# MK66F.net
KiCad netlist of a schematic drawn in Altium Designer
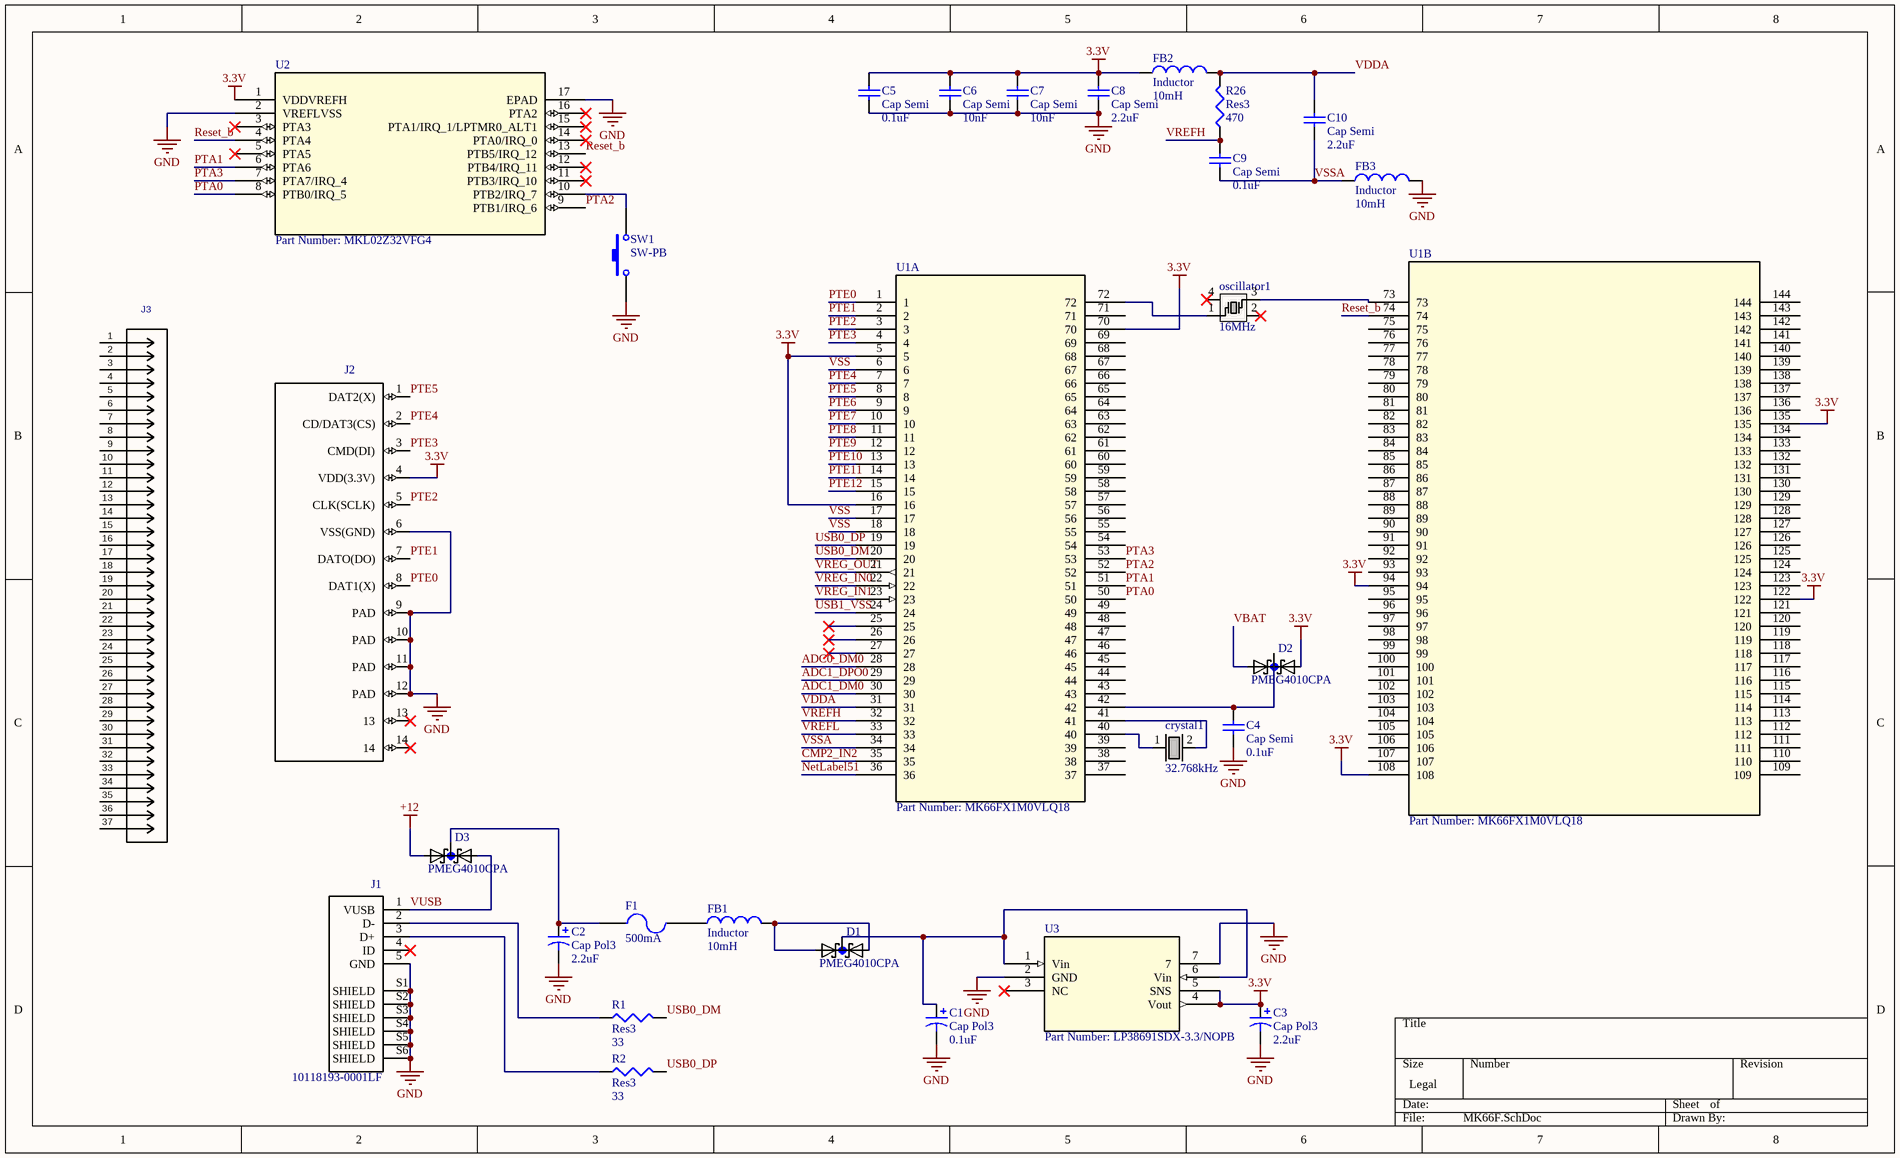
[diagram p0: MK66F.SchDoc]

(export (version "E")
  (design (tool "Eeschema 10.0.6"))
  (components
    (comp (ref "C1")
      (value "Cap Pol3")
      (footprint "C1206")
      (description "Polarized Capacitor (Surface Mount)")
      (fields (field (name "ALTIUM_VALUE") "0.1uF") (field (name "PUBLISHER") "Altium Limited"))
      (libsource (lib "Miscellaneous Devices") (part "Cap Pol3"))
    )
    (comp (ref "C2")
      (value "Cap Pol3")
      (footprint "C1206")
      (description "Polarized Capacitor (Surface Mount)")
      (fields (field (name "ALTIUM_VALUE") "2.2uF") (field (name "PUBLISHER") "Altium Limited"))
      (libsource (lib "Miscellaneous Devices") (part "Cap Pol3"))
    )
    (comp (ref "C3")
      (value "Cap Pol3")
      (footprint "C1206")
      (description "Polarized Capacitor (Surface Mount)")
      (fields (field (name "ALTIUM_VALUE") "2.2uF") (field (name "PUBLISHER") "Altium Limited"))
      (libsource (lib "Miscellaneous Devices") (part "Cap Pol3"))
    )
    (comp (ref "C4")
      (value "Cap Semi")
      (footprint "C1206")
      (description "Capacitor (Semiconductor SIM Model)")
      (fields (field (name "ALTIUM_VALUE") "0.1uF") (field (name "PUBLISHER") "Altium Limited"))
      (libsource (lib "Miscellaneous Devices") (part "Cap Semi"))
    )
    (comp (ref "C5")
      (value "Cap Semi")
      (footprint "C1206")
      (description "Capacitor (Semiconductor SIM Model)")
      (fields (field (name "ALTIUM_VALUE") "0.1uF") (field (name "PUBLISHER") "Altium Limited"))
      (libsource (lib "Miscellaneous Devices") (part "Cap Semi"))
    )
    (comp (ref "C6")
      (value "Cap Semi")
      (footprint "C1206")
      (description "Capacitor (Semiconductor SIM Model)")
      (fields (field (name "ALTIUM_VALUE") "10nF") (field (name "PUBLISHER") "Altium Limited"))
      (libsource (lib "Miscellaneous Devices") (part "Cap Semi"))
    )
    (comp (ref "C7")
      (value "Cap Semi")
      (footprint "C1206")
      (description "Capacitor (Semiconductor SIM Model)")
      (fields (field (name "ALTIUM_VALUE") "10nF") (field (name "PUBLISHER") "Altium Limited"))
      (libsource (lib "Miscellaneous Devices") (part "Cap Semi"))
    )
    (comp (ref "C8")
      (value "Cap Semi")
      (footprint "C1206")
      (description "Capacitor (Semiconductor SIM Model)")
      (fields (field (name "ALTIUM_VALUE") "2.2uF") (field (name "PUBLISHER") "Altium Limited"))
      (libsource (lib "Miscellaneous Devices") (part "Cap Semi"))
    )
    (comp (ref "C9")
      (value "Cap Semi")
      (footprint "C1206")
      (description "Capacitor (Semiconductor SIM Model)")
      (fields (field (name "ALTIUM_VALUE") "0.1uF") (field (name "PUBLISHER") "Altium Limited"))
      (libsource (lib "Miscellaneous Devices") (part "Cap Semi"))
    )
    (comp (ref "C10")
      (value "Cap Semi")
      (footprint "C1206")
      (description "Capacitor (Semiconductor SIM Model)")
      (fields (field (name "ALTIUM_VALUE") "2.2uF") (field (name "PUBLISHER") "Altium Limited"))
      (libsource (lib "Miscellaneous Devices") (part "Cap Semi"))
    )
    (comp (ref "crystal1")
      (value "32.768kHz")
      (footprint "ECS-.327-CDX-1128")
      (fields (field (name "Comment") "SMD_Crystal"))
      (libsource (lib "ECS-.327-CDX-1128") (part "ECS-.327-CDX-1128"))
    )
    (comp (ref "D1")
      (value "PMEG4010CPA")
      (footprint "*SOT1061")
      (fields (field (name "MF") "Nexperia USA") (field (name "DIGI-KEY_PART_NUMBER") "1727-5212-1-ND"))
      (libsource (lib "PMEG4010CPA") (part "PMEG4010CPA"))
    )
    (comp (ref "D2")
      (value "PMEG4010CPA")
      (footprint "*SOT1061")
      (fields (field (name "MF") "Nexperia USA") (field (name "DIGI-KEY_PART_NUMBER") "1727-5212-1-ND"))
      (libsource (lib "PMEG4010CPA") (part "PMEG4010CPA"))
    )
    (comp (ref "D3")
      (value "PMEG4010CPA")
      (footprint "*SOT1061")
      (fields (field (name "MF") "Nexperia USA") (field (name "DIGI-KEY_PART_NUMBER") "1727-5212-1-ND"))
      (libsource (lib "PMEG4010CPA") (part "PMEG4010CPA"))
    )
    (comp (ref "F1")
      (value "500mA")
      (footprint "RESC3216X125N")
      (description "Fuse")
      (fields (field (name "PUBLISHER") "Altium Limited"))
      (libsource (lib "Miscellaneous Devices") (part "Fuse 2"))
    )
    (comp (ref "FB1")
      (value "Inductor")
      (footprint "J1-0603")
      (fields (field (name "ALTIUM_VALUE") "10mH") (field (name "PUBLISHER") "Altium Limited"))
      (libsource (lib "Miscellaneous Devices") (part "Inductor"))
    )
    (comp (ref "FB2")
      (value "Inductor")
      (footprint "J1-0603")
      (fields (field (name "ALTIUM_VALUE") "10mH") (field (name "PUBLISHER") "Altium Limited"))
      (libsource (lib "Miscellaneous Devices") (part "Inductor"))
    )
    (comp (ref "FB3")
      (value "Inductor")
      (footprint "J1-0603")
      (fields (field (name "ALTIUM_VALUE") "10mH") (field (name "PUBLISHER") "Altium Limited"))
      (libsource (lib "Miscellaneous Devices") (part "Inductor"))
    )
    (comp (ref "J1")
      (value "10118193-0001LF")
      (footprint "FCI_10118193-0001LF_10118193-0001LF(Primary)")
      (description "Single Port 5 Contact Shielded SMT MICRO USB B-Type Receptacle")
      (fields (field (name "MF") "Amphenol FCI") (field (name "DIGI-KEY_PART_NUMBER") "609-4616-1-ND"))
      (libsource (lib "10118193-0001LF") (part "10118193-0001LF"))
    )
    (comp (ref "J2")
      (value "1140084168")
      (footprint "*1140084168")
      (description "Conn; IC Socket; Micro SD; Right Angle; PCB Mount; MicroSD Ser.")
      (fields (field (name "DIGI-KEY_PART_NUMBER") "114-00841-68-1-ND") (field (name "MF") "Amphenol ICC"))
      (libsource (lib "1140084168") (part "1140084168"))
    )
    (comp (ref "J3")
      (value "5747847-4")
      (footprint "SPGA48x11 - duplicate")
      (libsource (lib "5747847-4") (part "5747847-4"))
    )
    (comp (ref "oscillator1")
      (value "16MHz")
      (footprint "ECS-160-8-30B-CKM")
      (fields (field (name "Comment") "SMD_oscillator"))
      (libsource (lib "ECS-160-8-30B-CKM") (part "ECS-160-8-30B-CKM"))
    )
    (comp (ref "R1")
      (value "Res3")
      (footprint "J1-0603")
      (description "Resistor")
      (fields (field (name "ALTIUM_VALUE") "33") (field (name "PUBLISHER") "Altium Limited"))
      (libsource (lib "Miscellaneous Devices") (part "Res3"))
    )
    (comp (ref "R2")
      (value "Res3")
      (footprint "J1-0603")
      (description "Resistor")
      (fields (field (name "ALTIUM_VALUE") "33") (field (name "PUBLISHER") "Altium Limited"))
      (libsource (lib "Miscellaneous Devices") (part "Res3"))
    )
    (comp (ref "R26")
      (value "Res3")
      (footprint "J1-0603")
      (description "Resistor")
      (fields (field (name "ALTIUM_VALUE") "470") (field (name "PUBLISHER") "Altium Limited"))
      (libsource (lib "Miscellaneous Devices") (part "Res3"))
    )
    (comp (ref "SW1")
      (value "SW-PB")
      (footprint "P13348SCT-ND")
      (description "Switch")
      (fields (field (name "PUBLISHER") "Altium Limited"))
      (libsource (lib "Miscellaneous Devices") (part "SW-PB"))
    )
    (comp (ref "U1")
      (value "Part Number: MK66FX1M0VLQ18")
      (footprint "98ASS23177W")
      (description "No Description Available")
      (fields
        (field (name "MANUFACTURER_PART_NUMBER") "MK66FX1M0VLQ18")
        (field (name "COPYRIGHT") "Copyright (C) 2016 Accelerated Designs. All rights reserved")
      )
      (libsource (lib "2019-07-06_08-00-28") (part "MK66FX1M0VLQ18"))
    )
    (comp (ref "U2")
      (value "Part Number: MKL02Z32VFG4")
      (footprint "QFN-16_3X3X0.65")
      (description "No Description Available")
      (fields
        (field (name "MANUFACTURER_PART_NUMBER") "MKL02Z32VFG4")
        (field (name "COPYRIGHT") "Copyright (C) 2016 Accelerated Designs. All rights reserved")
      )
      (libsource (lib "2019-07-30_08-24-30") (part "MKL02Z32VFG4"))
    )
    (comp (ref "U3")
      (value "Part Number: LP38691SDX-3.3/NOPB")
      (footprint "SDE06A")
      (description "No Description Available")
      (fields
        (field (name "MANUFACTURER_PART_NUMBER") "LP38691SDX-3.3/NOPB")
        (field (name "COPYRIGHT") "Copyright (C) 2018 Accelerated Designs. All rights reserved")
      )
      (libsource (lib "LP38691SDX_3") (part "LP38691SDX-3.3/N"))
    )
  )
  (nets
    (net (code "1") (name "+12") (class "Default")
      (node (ref "D3") (pin "1") (pinfunction "A1_1") (pintype "passive"))
    )
    (net (code "2") (name "/ADC0_DM0") (class "Default")
      (node (ref "U1") (pin "28") (pinfunction "28_28") (pintype "passive"))
    )
    (net (code "3") (name "/ADC1_DM0") (class "Default")
      (node (ref "U1") (pin "30") (pinfunction "30_30") (pintype "passive"))
    )
    (net (code "4") (name "/ADC1_DPO0") (class "Default")
      (node (ref "U1") (pin "29") (pinfunction "29_29") (pintype "passive"))
    )
    (net (code "5") (name "/CMP2_IN2") (class "Default")
      (node (ref "U1") (pin "35") (pinfunction "35_35") (pintype "passive"))
    )
    (net (code "6") (name "/NetLabel51") (class "Default")
      (node (ref "U1") (pin "36") (pinfunction "36_36") (pintype "passive"))
    )
    (net (code "7") (name "/PTA0") (class "Default")
      (node (ref "U1") (pin "50") (pinfunction "50_50") (pintype "passive"))
      (node (ref "U2") (pin "8") (pinfunction "PTB0/IRQ_5_8") (pintype "bidirectional"))
    )
    (net (code "8") (name "/PTA1") (class "Default")
      (node (ref "U1") (pin "51") (pinfunction "51_51") (pintype "passive"))
      (node (ref "U2") (pin "6") (pinfunction "PTA6_6") (pintype "bidirectional"))
    )
    (net (code "9") (name "/PTA2") (class "Default")
      (node (ref "U1") (pin "52") (pinfunction "52_52") (pintype "passive"))
      (node (ref "U2") (pin "9") (pinfunction "PTB1/IRQ_6_9") (pintype "bidirectional"))
    )
    (net (code "10") (name "/PTA3") (class "Default")
      (node (ref "U1") (pin "53") (pinfunction "53_53") (pintype "passive"))
      (node (ref "U2") (pin "7") (pinfunction "PTA7/IRQ_4_7") (pintype "bidirectional"))
    )
    (net (code "11") (name "/PTE0") (class "Default")
      (node (ref "J2") (pin "8") (pinfunction "DAT1(X)_8") (pintype "bidirectional"))
      (node (ref "U1") (pin "1") (pinfunction "1_1") (pintype "passive"))
    )
    (net (code "12") (name "/PTE1") (class "Default")
      (node (ref "J2") (pin "7") (pinfunction "DATO(DO)_7") (pintype "bidirectional"))
      (node (ref "U1") (pin "2") (pinfunction "2_2") (pintype "passive"))
    )
    (net (code "13") (name "/PTE2") (class "Default")
      (node (ref "J2") (pin "5") (pinfunction "CLK(SCLK)_5") (pintype "bidirectional"))
      (node (ref "U1") (pin "3") (pinfunction "3_3") (pintype "passive"))
    )
    (net (code "14") (name "/PTE3") (class "Default")
      (node (ref "J2") (pin "3") (pinfunction "CMD(DI)_3") (pintype "bidirectional"))
      (node (ref "U1") (pin "4") (pinfunction "4_4") (pintype "passive"))
    )
    (net (code "15") (name "/PTE4") (class "Default")
      (node (ref "J2") (pin "2") (pinfunction "CD/DAT3(CS)_2") (pintype "bidirectional"))
      (node (ref "U1") (pin "7") (pinfunction "7_7") (pintype "passive"))
    )
    (net (code "16") (name "/PTE5") (class "Default")
      (node (ref "J2") (pin "1") (pinfunction "DAT2(X)_1") (pintype "bidirectional"))
      (node (ref "U1") (pin "8") (pinfunction "8_8") (pintype "passive"))
    )
    (net (code "17") (name "/PTE6") (class "Default")
      (node (ref "U1") (pin "9") (pinfunction "9_9") (pintype "passive"))
    )
    (net (code "18") (name "/PTE7") (class "Default")
      (node (ref "U1") (pin "10") (pinfunction "10_10") (pintype "passive"))
    )
    (net (code "19") (name "/PTE8") (class "Default")
      (node (ref "U1") (pin "11") (pinfunction "11_11") (pintype "passive"))
    )
    (net (code "20") (name "/PTE9") (class "Default")
      (node (ref "U1") (pin "12") (pinfunction "12_12") (pintype "passive"))
    )
    (net (code "21") (name "/PTE10") (class "Default")
      (node (ref "U1") (pin "13") (pinfunction "13_13") (pintype "passive"))
    )
    (net (code "22") (name "/PTE11") (class "Default")
      (node (ref "U1") (pin "14") (pinfunction "14_14") (pintype "passive"))
    )
    (net (code "23") (name "/PTE12") (class "Default")
      (node (ref "U1") (pin "15") (pinfunction "15_15") (pintype "passive"))
    )
    (net (code "24") (name "/Reset_b") (class "Default")
      (node (ref "U1") (pin "74") (pinfunction "74_74") (pintype "passive"))
      (node (ref "U2") (pin "13") (pinfunction "PTB5/IRQ_12_13") (pintype "bidirectional"))
      (node (ref "U2") (pin "4") (pinfunction "PTA4_4") (pintype "bidirectional"))
    )
    (net (code "25") (name "/USB0_DM") (class "Default")
      (node (ref "R1") (pin "2") (pinfunction "2_2") (pintype "passive"))
      (node (ref "U1") (pin "20") (pinfunction "20_20") (pintype "passive"))
    )
    (net (code "26") (name "/USB0_DP") (class "Default")
      (node (ref "R2") (pin "2") (pinfunction "2_2") (pintype "passive"))
      (node (ref "U1") (pin "19") (pinfunction "19_19") (pintype "passive"))
    )
    (net (code "27") (name "/USB1_VSS") (class "Default")
      (node (ref "U1") (pin "24") (pinfunction "24_24") (pintype "power_in"))
    )
    (net (code "28") (name "/VBAT") (class "Default")
      (node (ref "D2") (pin "1") (pinfunction "A1_1") (pintype "passive"))
    )
    (net (code "29") (name "/VDDA") (class "Default")
      (node (ref "C10") (pin "2") (pinfunction "2_2") (pintype "passive"))
      (node (ref "FB2") (pin "2") (pinfunction "2_2") (pintype "passive"))
      (node (ref "R26") (pin "2") (pinfunction "2_2") (pintype "passive"))
      (node (ref "U1") (pin "31") (pinfunction "31_31") (pintype "power_in"))
    )
    (net (code "30") (name "/VREFH") (class "Default")
      (node (ref "C9") (pin "2") (pinfunction "2_2") (pintype "passive"))
      (node (ref "R26") (pin "1") (pinfunction "1_1") (pintype "passive"))
      (node (ref "U1") (pin "32") (pinfunction "32_32") (pintype "power_in"))
    )
    (net (code "31") (name "/VREFL") (class "Default")
      (node (ref "U1") (pin "33") (pinfunction "33_33") (pintype "power_in"))
    )
    (net (code "32") (name "/VREG_IN0") (class "Default")
      (node (ref "U1") (pin "22") (pinfunction "22_22") (pintype "input"))
    )
    (net (code "33") (name "/VREG_IN1") (class "Default")
      (node (ref "U1") (pin "23") (pinfunction "23_23") (pintype "input"))
    )
    (net (code "34") (name "/VREG_OUT") (class "Default")
      (node (ref "U1") (pin "21") (pinfunction "21_21") (pintype "output"))
    )
    (net (code "35") (name "/VSS") (class "Default")
      (node (ref "U1") (pin "17") (pinfunction "17_17") (pintype "power_in"))
      (node (ref "U1") (pin "18") (pinfunction "18_18") (pintype "power_in"))
      (node (ref "U1") (pin "6") (pinfunction "6_6") (pintype "power_in"))
    )
    (net (code "36") (name "/VSSA") (class "Default")
      (node (ref "C10") (pin "1") (pinfunction "1_1") (pintype "passive"))
      (node (ref "C9") (pin "1") (pinfunction "1_1") (pintype "passive"))
      (node (ref "FB3") (pin "1") (pinfunction "1_1") (pintype "passive"))
      (node (ref "U1") (pin "34") (pinfunction "34_34") (pintype "power_in"))
    )
    (net (code "37") (name "/VUSB") (class "Default")
      (node (ref "D3") (pin "2") (pinfunction "A2_2") (pintype "passive"))
      (node (ref "J1") (pin "1") (pinfunction "VUSB_1") (pintype "passive"))
    )
    (net (code "38") (name "3.3V") (class "Default")
      (node (ref "C3") (pin "1") (pinfunction "1_1") (pintype "passive"))
      (node (ref "C5") (pin "2") (pinfunction "2_2") (pintype "passive"))
      (node (ref "C6") (pin "2") (pinfunction "2_2") (pintype "passive"))
      (node (ref "C7") (pin "2") (pinfunction "2_2") (pintype "passive"))
      (node (ref "C8") (pin "2") (pinfunction "2_2") (pintype "passive"))
      (node (ref "D2") (pin "2") (pinfunction "A2_2") (pintype "passive"))
      (node (ref "FB2") (pin "1") (pinfunction "1_1") (pintype "passive"))
      (node (ref "J2") (pin "4") (pinfunction "VDD(3.3V)_4") (pintype "bidirectional"))
      (node (ref "U1") (pin "108") (pinfunction "108_108") (pintype "power_in"))
      (node (ref "U1") (pin "122") (pinfunction "122_122") (pintype "power_in"))
      (node (ref "U1") (pin "135") (pinfunction "135_135") (pintype "power_in"))
      (node (ref "U1") (pin "16") (pinfunction "16_16") (pintype "power_in"))
      (node (ref "U1") (pin "5") (pinfunction "5_5") (pintype "power_in"))
      (node (ref "U1") (pin "70") (pinfunction "70_70") (pintype "power_in"))
      (node (ref "U1") (pin "94") (pinfunction "94_94") (pintype "power_in"))
      (node (ref "U2") (pin "1") (pinfunction "VDDVREFH_1") (pintype "power_in"))
      (node (ref "U3") (pin "4") (pinfunction "Vout_4") (pintype "output"))
      (node (ref "U3") (pin "5") (pinfunction "SNS_5") (pintype "passive"))
    )
    (net (code "39") (name "GND") (class "Default")
      (node (ref "C1") (pin "2") (pinfunction "2_2") (pintype "passive"))
      (node (ref "C2") (pin "2") (pinfunction "2_2") (pintype "passive"))
      (node (ref "C3") (pin "2") (pinfunction "2_2") (pintype "passive"))
      (node (ref "C4") (pin "1") (pinfunction "1_1") (pintype "passive"))
      (node (ref "C5") (pin "1") (pinfunction "1_1") (pintype "passive"))
      (node (ref "C6") (pin "1") (pinfunction "1_1") (pintype "passive"))
      (node (ref "C7") (pin "1") (pinfunction "1_1") (pintype "passive"))
      (node (ref "C8") (pin "1") (pinfunction "1_1") (pintype "passive"))
      (node (ref "FB3") (pin "2") (pinfunction "2_2") (pintype "passive"))
      (node (ref "J1") (pin "5") (pinfunction "GND_5") (pintype "passive"))
      (node (ref "J1") (pin "S1") (pinfunction "SHIELD_S1") (pintype "passive"))
      (node (ref "J1") (pin "S2") (pinfunction "SHIELD_S2") (pintype "passive"))
      (node (ref "J1") (pin "S3") (pinfunction "SHIELD_S3") (pintype "passive"))
      (node (ref "J1") (pin "S4") (pinfunction "SHIELD_S4") (pintype "passive"))
      (node (ref "J1") (pin "S5") (pinfunction "SHIELD_S5") (pintype "passive"))
      (node (ref "J1") (pin "S6") (pinfunction "SHIELD_S6") (pintype "passive"))
      (node (ref "J2") (pin "10") (pinfunction "PAD_10") (pintype "bidirectional"))
      (node (ref "J2") (pin "11") (pinfunction "PAD_11") (pintype "bidirectional"))
      (node (ref "J2") (pin "12") (pinfunction "PAD_12") (pintype "bidirectional"))
      (node (ref "J2") (pin "6") (pinfunction "VSS(GND)_6") (pintype "bidirectional"))
      (node (ref "J2") (pin "9") (pinfunction "PAD_9") (pintype "bidirectional"))
      (node (ref "SW1") (pin "1") (pinfunction "1_1") (pintype "passive"))
      (node (ref "U2") (pin "17") (pinfunction "EPAD_17") (pintype "passive"))
      (node (ref "U2") (pin "2") (pinfunction "VREFLVSS_2") (pintype "power_in"))
      (node (ref "U3") (pin "2") (pinfunction "GND_2") (pintype "passive"))
      (node (ref "U3") (pin "7") (pinfunction "7_7") (pintype "passive"))
    )
    (net (code "40") (name "Net-(C4-Pad2)") (class "Default")
      (node (ref "C4") (pin "2") (pinfunction "2_2") (pintype "passive"))
      (node (ref "U1") (pin "42") (pinfunction "42_42") (pintype "power_in"))
    )
    (net (code "41") (name "Net-(D1-A1)") (class "Default")
      (node (ref "D1") (pin "1") (pinfunction "A1_1") (pintype "passive"))
      (node (ref "D1") (pin "2") (pinfunction "A2_2") (pintype "passive"))
      (node (ref "FB1") (pin "2") (pinfunction "2_2") (pintype "passive"))
    )
    (net (code "42") (name "Net-(D1-K1K2)") (class "Default")
      (node (ref "C1") (pin "1") (pinfunction "1_1") (pintype "passive"))
      (node (ref "D1") (pin "3") (pinfunction "K1K2_3") (pintype "passive"))
      (node (ref "U3") (pin "1") (pinfunction "Vin_1") (pintype "input"))
      (node (ref "U3") (pin "6") (pinfunction "Vin_6") (pintype "input"))
    )
    (net (code "43") (name "Net-(D3-K1K2)") (class "Default")
      (node (ref "C2") (pin "1") (pinfunction "1_1") (pintype "passive"))
      (node (ref "D3") (pin "3") (pinfunction "K1K2_3") (pintype "passive"))
      (node (ref "F1") (pin "1") (pinfunction "1_1") (pintype "passive"))
    )
    (net (code "44") (name "Net-(F1-Pad2)") (class "Default")
      (node (ref "F1") (pin "2") (pinfunction "2_2") (pintype "passive"))
      (node (ref "FB1") (pin "1") (pinfunction "1_1") (pintype "passive"))
    )
    (net (code "45") (name "Net-(J1-D+)") (class "Default")
      (node (ref "J1") (pin "3") (pinfunction "D+_3") (pintype "passive"))
      (node (ref "R2") (pin "1") (pinfunction "1_1") (pintype "passive"))
    )
    (net (code "46") (name "Net-(J1-D-)") (class "Default")
      (node (ref "J1") (pin "2") (pinfunction "D-_2") (pintype "passive"))
      (node (ref "R1") (pin "1") (pinfunction "1_1") (pintype "passive"))
    )
    (net (code "47") (name "Net-(U1-Pad40)") (class "Default")
      (node (ref "U1") (pin "40") (pinfunction "40_40") (pintype "passive"))
      (node (ref "crystal1") (pin "1") (pinfunction "1_1") (pintype "passive"))
    )
    (net (code "48") (name "Net-(U1-Pad41)") (class "Default")
      (node (ref "U1") (pin "41") (pinfunction "41_41") (pintype "passive"))
      (node (ref "crystal1") (pin "2") (pinfunction "2_2") (pintype "passive"))
    )
    (net (code "49") (name "Net-(U1-Pad72)") (class "Default")
      (node (ref "U1") (pin "72") (pinfunction "72_72") (pintype "passive"))
      (node (ref "oscillator1") (pin "1") (pinfunction "1_1") (pintype "passive"))
    )
    (net (code "50") (name "Net-(U1-Pad73)") (class "Default")
      (node (ref "U1") (pin "73") (pinfunction "73_73") (pintype "passive"))
      (node (ref "oscillator1") (pin "3") (pinfunction "3_3") (pintype "passive"))
    )
    (net (code "51") (name "Net-(U2-PTB2{slash}IRQ_7)") (class "Default")
      (node (ref "SW1") (pin "2") (pinfunction "2_2") (pintype "passive"))
      (node (ref "U2") (pin "10") (pinfunction "PTB2/IRQ_7_10") (pintype "bidirectional"))
    )
    (net (code "52") (name "unconnected-(D2-K1K2-Pad3)") (class "Default")
      (node (ref "D2") (pin "3") (pinfunction "K1K2_3") (pintype "passive"))
    )
    (net (code "53") (name "unconnected-(J1-ID-Pad4)") (class "Default")
      (node (ref "J1") (pin "4") (pinfunction "ID_4") (pintype "passive+no_connect"))
    )
    (net (code "54") (name "unconnected-(J2-Pad13)") (class "Default")
      (node (ref "J2") (pin "13") (pinfunction "13_13") (pintype "bidirectional+no_connect"))
    )
    (net (code "55") (name "unconnected-(J2-Pad14)") (class "Default")
      (node (ref "J2") (pin "14") (pinfunction "14_14") (pintype "bidirectional+no_connect"))
    )
    (net (code "56") (name "unconnected-(J3-Pad1)") (class "Default")
      (node (ref "J3") (pin "1") (pinfunction "1_1") (pintype "passive"))
    )
    (net (code "57") (name "unconnected-(J3-Pad2)") (class "Default")
      (node (ref "J3") (pin "2") (pinfunction "2_2") (pintype "passive"))
    )
    (net (code "58") (name "unconnected-(J3-Pad3)") (class "Default")
      (node (ref "J3") (pin "3") (pinfunction "3_3") (pintype "passive"))
    )
    (net (code "59") (name "unconnected-(J3-Pad4)") (class "Default")
      (node (ref "J3") (pin "4") (pinfunction "4_4") (pintype "passive"))
    )
    (net (code "60") (name "unconnected-(J3-Pad5)") (class "Default")
      (node (ref "J3") (pin "5") (pinfunction "5_5") (pintype "passive"))
    )
    (net (code "61") (name "unconnected-(J3-Pad6)") (class "Default")
      (node (ref "J3") (pin "6") (pinfunction "6_6") (pintype "passive"))
    )
    (net (code "62") (name "unconnected-(J3-Pad7)") (class "Default")
      (node (ref "J3") (pin "7") (pinfunction "7_7") (pintype "passive"))
    )
    (net (code "63") (name "unconnected-(J3-Pad8)") (class "Default")
      (node (ref "J3") (pin "8") (pinfunction "8_8") (pintype "passive"))
    )
    (net (code "64") (name "unconnected-(J3-Pad9)") (class "Default")
      (node (ref "J3") (pin "9") (pinfunction "9_9") (pintype "passive"))
    )
    (net (code "65") (name "unconnected-(J3-Pad10)") (class "Default")
      (node (ref "J3") (pin "10") (pinfunction "10_10") (pintype "passive"))
    )
    (net (code "66") (name "unconnected-(J3-Pad11)") (class "Default")
      (node (ref "J3") (pin "11") (pinfunction "11_11") (pintype "passive"))
    )
    (net (code "67") (name "unconnected-(J3-Pad12)") (class "Default")
      (node (ref "J3") (pin "12") (pinfunction "12_12") (pintype "passive"))
    )
    (net (code "68") (name "unconnected-(J3-Pad13)") (class "Default")
      (node (ref "J3") (pin "13") (pinfunction "13_13") (pintype "passive"))
    )
    (net (code "69") (name "unconnected-(J3-Pad14)") (class "Default")
      (node (ref "J3") (pin "14") (pinfunction "14_14") (pintype "passive"))
    )
    (net (code "70") (name "unconnected-(J3-Pad15)") (class "Default")
      (node (ref "J3") (pin "15") (pinfunction "15_15") (pintype "passive"))
    )
    (net (code "71") (name "unconnected-(J3-Pad16)") (class "Default")
      (node (ref "J3") (pin "16") (pinfunction "16_16") (pintype "passive"))
    )
    (net (code "72") (name "unconnected-(J3-Pad17)") (class "Default")
      (node (ref "J3") (pin "17") (pinfunction "17_17") (pintype "passive"))
    )
    (net (code "73") (name "unconnected-(J3-Pad18)") (class "Default")
      (node (ref "J3") (pin "18") (pinfunction "18_18") (pintype "passive"))
    )
    (net (code "74") (name "unconnected-(J3-Pad19)") (class "Default")
      (node (ref "J3") (pin "19") (pinfunction "19_19") (pintype "passive"))
    )
    (net (code "75") (name "unconnected-(J3-Pad20)") (class "Default")
      (node (ref "J3") (pin "20") (pinfunction "20_20") (pintype "passive"))
    )
    (net (code "76") (name "unconnected-(J3-Pad21)") (class "Default")
      (node (ref "J3") (pin "21") (pinfunction "21_21") (pintype "passive"))
    )
    (net (code "77") (name "unconnected-(J3-Pad22)") (class "Default")
      (node (ref "J3") (pin "22") (pinfunction "22_22") (pintype "passive"))
    )
    (net (code "78") (name "unconnected-(J3-Pad23)") (class "Default")
      (node (ref "J3") (pin "23") (pinfunction "23_23") (pintype "passive"))
    )
    (net (code "79") (name "unconnected-(J3-Pad24)") (class "Default")
      (node (ref "J3") (pin "24") (pinfunction "24_24") (pintype "passive"))
    )
    (net (code "80") (name "unconnected-(J3-Pad25)") (class "Default")
      (node (ref "J3") (pin "25") (pinfunction "25_25") (pintype "passive"))
    )
    (net (code "81") (name "unconnected-(J3-Pad26)") (class "Default")
      (node (ref "J3") (pin "26") (pinfunction "26_26") (pintype "passive"))
    )
    (net (code "82") (name "unconnected-(J3-Pad27)") (class "Default")
      (node (ref "J3") (pin "27") (pinfunction "27_27") (pintype "passive"))
    )
    (net (code "83") (name "unconnected-(J3-Pad28)") (class "Default")
      (node (ref "J3") (pin "28") (pinfunction "28_28") (pintype "passive"))
    )
    (net (code "84") (name "unconnected-(J3-Pad29)") (class "Default")
      (node (ref "J3") (pin "29") (pinfunction "29_29") (pintype "passive"))
    )
    (net (code "85") (name "unconnected-(J3-Pad30)") (class "Default")
      (node (ref "J3") (pin "30") (pinfunction "30_30") (pintype "passive"))
    )
    (net (code "86") (name "unconnected-(J3-Pad31)") (class "Default")
      (node (ref "J3") (pin "31") (pinfunction "31_31") (pintype "passive"))
    )
    (net (code "87") (name "unconnected-(J3-Pad32)") (class "Default")
      (node (ref "J3") (pin "32") (pinfunction "32_32") (pintype "passive"))
    )
    (net (code "88") (name "unconnected-(J3-Pad33)") (class "Default")
      (node (ref "J3") (pin "33") (pinfunction "33_33") (pintype "passive"))
    )
    (net (code "89") (name "unconnected-(J3-Pad34)") (class "Default")
      (node (ref "J3") (pin "34") (pinfunction "34_34") (pintype "passive"))
    )
    (net (code "90") (name "unconnected-(J3-Pad35)") (class "Default")
      (node (ref "J3") (pin "35") (pinfunction "35_35") (pintype "passive"))
    )
    (net (code "91") (name "unconnected-(J3-Pad36)") (class "Default")
      (node (ref "J3") (pin "36") (pinfunction "36_36") (pintype "passive"))
    )
    (net (code "92") (name "unconnected-(J3-Pad37)") (class "Default")
      (node (ref "J3") (pin "37") (pinfunction "37_37") (pintype "passive"))
    )
    (net (code "93") (name "unconnected-(U1-Pad25)") (class "Default")
      (node (ref "U1") (pin "25") (pinfunction "25_25") (pintype "passive+no_connect"))
    )
    (net (code "94") (name "unconnected-(U1-Pad26)") (class "Default")
      (node (ref "U1") (pin "26") (pinfunction "26_26") (pintype "passive+no_connect"))
    )
    (net (code "95") (name "unconnected-(U1-Pad27)") (class "Default")
      (node (ref "U1") (pin "27") (pinfunction "27_27") (pintype "passive+no_connect"))
    )
    (net (code "96") (name "unconnected-(U1-Pad37)") (class "Default")
      (node (ref "U1") (pin "37") (pinfunction "37_37") (pintype "passive"))
    )
    (net (code "97") (name "unconnected-(U1-Pad38)") (class "Default")
      (node (ref "U1") (pin "38") (pinfunction "38_38") (pintype "passive"))
    )
    (net (code "98") (name "unconnected-(U1-Pad39)") (class "Default")
      (node (ref "U1") (pin "39") (pinfunction "39_39") (pintype "passive"))
    )
    (net (code "99") (name "unconnected-(U1-Pad43)") (class "Default")
      (node (ref "U1") (pin "43") (pinfunction "43_43") (pintype "power_in"))
    )
    (net (code "100") (name "unconnected-(U1-Pad44)") (class "Default")
      (node (ref "U1") (pin "44") (pinfunction "44_44") (pintype "power_in"))
    )
    (net (code "101") (name "unconnected-(U1-Pad45)") (class "Default")
      (node (ref "U1") (pin "45") (pinfunction "45_45") (pintype "passive"))
    )
    (net (code "102") (name "unconnected-(U1-Pad46)") (class "Default")
      (node (ref "U1") (pin "46") (pinfunction "46_46") (pintype "passive"))
    )
    (net (code "103") (name "unconnected-(U1-Pad47)") (class "Default")
      (node (ref "U1") (pin "47") (pinfunction "47_47") (pintype "passive"))
    )
    (net (code "104") (name "unconnected-(U1-Pad48)") (class "Default")
      (node (ref "U1") (pin "48") (pinfunction "48_48") (pintype "passive"))
    )
    (net (code "105") (name "unconnected-(U1-Pad49)") (class "Default")
      (node (ref "U1") (pin "49") (pinfunction "49_49") (pintype "passive"))
    )
    (net (code "106") (name "unconnected-(U1-Pad54)") (class "Default")
      (node (ref "U1") (pin "54") (pinfunction "54_54") (pintype "passive"))
    )
    (net (code "107") (name "unconnected-(U1-Pad55)") (class "Default")
      (node (ref "U1") (pin "55") (pinfunction "55_55") (pintype "passive"))
    )
    (net (code "108") (name "unconnected-(U1-Pad56)") (class "Default")
      (node (ref "U1") (pin "56") (pinfunction "56_56") (pintype "power_in"))
    )
    (net (code "109") (name "unconnected-(U1-Pad57)") (class "Default")
      (node (ref "U1") (pin "57") (pinfunction "57_57") (pintype "power_in"))
    )
    (net (code "110") (name "unconnected-(U1-Pad58)") (class "Default")
      (node (ref "U1") (pin "58") (pinfunction "58_58") (pintype "passive"))
    )
    (net (code "111") (name "unconnected-(U1-Pad59)") (class "Default")
      (node (ref "U1") (pin "59") (pinfunction "59_59") (pintype "passive"))
    )
    (net (code "112") (name "unconnected-(U1-Pad60)") (class "Default")
      (node (ref "U1") (pin "60") (pinfunction "60_60") (pintype "passive"))
    )
    (net (code "113") (name "unconnected-(U1-Pad61)") (class "Default")
      (node (ref "U1") (pin "61") (pinfunction "61_61") (pintype "passive"))
    )
    (net (code "114") (name "unconnected-(U1-Pad62)") (class "Default")
      (node (ref "U1") (pin "62") (pinfunction "62_62") (pintype "passive"))
    )
    (net (code "115") (name "unconnected-(U1-Pad63)") (class "Default")
      (node (ref "U1") (pin "63") (pinfunction "63_63") (pintype "passive"))
    )
    (net (code "116") (name "unconnected-(U1-Pad64)") (class "Default")
      (node (ref "U1") (pin "64") (pinfunction "64_64") (pintype "passive"))
    )
    (net (code "117") (name "unconnected-(U1-Pad65)") (class "Default")
      (node (ref "U1") (pin "65") (pinfunction "65_65") (pintype "passive"))
    )
    (net (code "118") (name "unconnected-(U1-Pad66)") (class "Default")
      (node (ref "U1") (pin "66") (pinfunction "66_66") (pintype "passive"))
    )
    (net (code "119") (name "unconnected-(U1-Pad67)") (class "Default")
      (node (ref "U1") (pin "67") (pinfunction "67_67") (pintype "passive"))
    )
    (net (code "120") (name "unconnected-(U1-Pad68)") (class "Default")
      (node (ref "U1") (pin "68") (pinfunction "68_68") (pintype "passive"))
    )
    (net (code "121") (name "unconnected-(U1-Pad69)") (class "Default")
      (node (ref "U1") (pin "69") (pinfunction "69_69") (pintype "passive"))
    )
    (net (code "122") (name "unconnected-(U1-Pad71)") (class "Default")
      (node (ref "U1") (pin "71") (pinfunction "71_71") (pintype "power_in"))
    )
    (net (code "123") (name "unconnected-(U1-Pad75)") (class "Default")
      (node (ref "U1") (pin "75") (pinfunction "75_75") (pintype "passive"))
    )
    (net (code "124") (name "unconnected-(U1-Pad76)") (class "Default")
      (node (ref "U1") (pin "76") (pinfunction "76_76") (pintype "passive"))
    )
    (net (code "125") (name "unconnected-(U1-Pad77)") (class "Default")
      (node (ref "U1") (pin "77") (pinfunction "77_77") (pintype "passive"))
    )
    (net (code "126") (name "unconnected-(U1-Pad78)") (class "Default")
      (node (ref "U1") (pin "78") (pinfunction "78_78") (pintype "passive"))
    )
    (net (code "127") (name "unconnected-(U1-Pad79)") (class "Default")
      (node (ref "U1") (pin "79") (pinfunction "79_79") (pintype "passive"))
    )
    (net (code "128") (name "unconnected-(U1-Pad80)") (class "Default")
      (node (ref "U1") (pin "80") (pinfunction "80_80") (pintype "passive"))
    )
    (net (code "129") (name "unconnected-(U1-Pad81)") (class "Default")
      (node (ref "U1") (pin "81") (pinfunction "81_81") (pintype "passive"))
    )
    (net (code "130") (name "unconnected-(U1-Pad82)") (class "Default")
      (node (ref "U1") (pin "82") (pinfunction "82_82") (pintype "passive"))
    )
    (net (code "131") (name "unconnected-(U1-Pad83)") (class "Default")
      (node (ref "U1") (pin "83") (pinfunction "83_83") (pintype "passive"))
    )
    (net (code "132") (name "unconnected-(U1-Pad84)") (class "Default")
      (node (ref "U1") (pin "84") (pinfunction "84_84") (pintype "passive"))
    )
    (net (code "133") (name "unconnected-(U1-Pad85)") (class "Default")
      (node (ref "U1") (pin "85") (pinfunction "85_85") (pintype "passive"))
    )
    (net (code "134") (name "unconnected-(U1-Pad86)") (class "Default")
      (node (ref "U1") (pin "86") (pinfunction "86_86") (pintype "passive"))
    )
    (net (code "135") (name "unconnected-(U1-Pad87)") (class "Default")
      (node (ref "U1") (pin "87") (pinfunction "87_87") (pintype "passive"))
    )
    (net (code "136") (name "unconnected-(U1-Pad88)") (class "Default")
      (node (ref "U1") (pin "88") (pinfunction "88_88") (pintype "passive"))
    )
    (net (code "137") (name "unconnected-(U1-Pad89)") (class "Default")
      (node (ref "U1") (pin "89") (pinfunction "89_89") (pintype "passive"))
    )
    (net (code "138") (name "unconnected-(U1-Pad90)") (class "Default")
      (node (ref "U1") (pin "90") (pinfunction "90_90") (pintype "passive"))
    )
    (net (code "139") (name "unconnected-(U1-Pad91)") (class "Default")
      (node (ref "U1") (pin "91") (pinfunction "91_91") (pintype "passive"))
    )
    (net (code "140") (name "unconnected-(U1-Pad92)") (class "Default")
      (node (ref "U1") (pin "92") (pinfunction "92_92") (pintype "passive"))
    )
    (net (code "141") (name "unconnected-(U1-Pad93)") (class "Default")
      (node (ref "U1") (pin "93") (pinfunction "93_93") (pintype "power_in"))
    )
    (net (code "142") (name "unconnected-(U1-Pad95)") (class "Default")
      (node (ref "U1") (pin "95") (pinfunction "95_95") (pintype "passive"))
    )
    (net (code "143") (name "unconnected-(U1-Pad96)") (class "Default")
      (node (ref "U1") (pin "96") (pinfunction "96_96") (pintype "passive"))
    )
    (net (code "144") (name "unconnected-(U1-Pad97)") (class "Default")
      (node (ref "U1") (pin "97") (pinfunction "97_97") (pintype "passive"))
    )
    (net (code "145") (name "unconnected-(U1-Pad98)") (class "Default")
      (node (ref "U1") (pin "98") (pinfunction "98_98") (pintype "passive"))
    )
    (net (code "146") (name "unconnected-(U1-Pad99)") (class "Default")
      (node (ref "U1") (pin "99") (pinfunction "99_99") (pintype "passive"))
    )
    (net (code "147") (name "unconnected-(U1-Pad100)") (class "Default")
      (node (ref "U1") (pin "100") (pinfunction "100_100") (pintype "passive"))
    )
    (net (code "148") (name "unconnected-(U1-Pad101)") (class "Default")
      (node (ref "U1") (pin "101") (pinfunction "101_101") (pintype "passive"))
    )
    (net (code "149") (name "unconnected-(U1-Pad102)") (class "Default")
      (node (ref "U1") (pin "102") (pinfunction "102_102") (pintype "passive"))
    )
    (net (code "150") (name "unconnected-(U1-Pad103)") (class "Default")
      (node (ref "U1") (pin "103") (pinfunction "103_103") (pintype "passive"))
    )
    (net (code "151") (name "unconnected-(U1-Pad104)") (class "Default")
      (node (ref "U1") (pin "104") (pinfunction "104_104") (pintype "passive"))
    )
    (net (code "152") (name "unconnected-(U1-Pad105)") (class "Default")
      (node (ref "U1") (pin "105") (pinfunction "105_105") (pintype "passive"))
    )
    (net (code "153") (name "unconnected-(U1-Pad106)") (class "Default")
      (node (ref "U1") (pin "106") (pinfunction "106_106") (pintype "passive"))
    )
    (net (code "154") (name "unconnected-(U1-Pad107)") (class "Default")
      (node (ref "U1") (pin "107") (pinfunction "107_107") (pintype "power_in"))
    )
    (net (code "155") (name "unconnected-(U1-Pad109)") (class "Default")
      (node (ref "U1") (pin "109") (pinfunction "109_109") (pintype "passive"))
    )
    (net (code "156") (name "unconnected-(U1-Pad110)") (class "Default")
      (node (ref "U1") (pin "110") (pinfunction "110_110") (pintype "passive"))
    )
    (net (code "157") (name "unconnected-(U1-Pad111)") (class "Default")
      (node (ref "U1") (pin "111") (pinfunction "111_111") (pintype "passive"))
    )
    (net (code "158") (name "unconnected-(U1-Pad112)") (class "Default")
      (node (ref "U1") (pin "112") (pinfunction "112_112") (pintype "passive"))
    )
    (net (code "159") (name "unconnected-(U1-Pad113)") (class "Default")
      (node (ref "U1") (pin "113") (pinfunction "113_113") (pintype "passive"))
    )
    (net (code "160") (name "unconnected-(U1-Pad114)") (class "Default")
      (node (ref "U1") (pin "114") (pinfunction "114_114") (pintype "passive"))
    )
    (net (code "161") (name "unconnected-(U1-Pad115)") (class "Default")
      (node (ref "U1") (pin "115") (pinfunction "115_115") (pintype "passive"))
    )
    (net (code "162") (name "unconnected-(U1-Pad116)") (class "Default")
      (node (ref "U1") (pin "116") (pinfunction "116_116") (pintype "passive"))
    )
    (net (code "163") (name "unconnected-(U1-Pad117)") (class "Default")
      (node (ref "U1") (pin "117") (pinfunction "117_117") (pintype "passive"))
    )
    (net (code "164") (name "unconnected-(U1-Pad118)") (class "Default")
      (node (ref "U1") (pin "118") (pinfunction "118_118") (pintype "passive"))
    )
    (net (code "165") (name "unconnected-(U1-Pad119)") (class "Default")
      (node (ref "U1") (pin "119") (pinfunction "119_119") (pintype "passive"))
    )
    (net (code "166") (name "unconnected-(U1-Pad120)") (class "Default")
      (node (ref "U1") (pin "120") (pinfunction "120_120") (pintype "passive"))
    )
    (net (code "167") (name "unconnected-(U1-Pad121)") (class "Default")
      (node (ref "U1") (pin "121") (pinfunction "121_121") (pintype "power_in"))
    )
    (net (code "168") (name "unconnected-(U1-Pad123)") (class "Default")
      (node (ref "U1") (pin "123") (pinfunction "123_123") (pintype "passive"))
    )
    (net (code "169") (name "unconnected-(U1-Pad124)") (class "Default")
      (node (ref "U1") (pin "124") (pinfunction "124_124") (pintype "passive"))
    )
    (net (code "170") (name "unconnected-(U1-Pad125)") (class "Default")
      (node (ref "U1") (pin "125") (pinfunction "125_125") (pintype "passive"))
    )
    (net (code "171") (name "unconnected-(U1-Pad126)") (class "Default")
      (node (ref "U1") (pin "126") (pinfunction "126_126") (pintype "passive"))
    )
    (net (code "172") (name "unconnected-(U1-Pad127)") (class "Default")
      (node (ref "U1") (pin "127") (pinfunction "127_127") (pintype "passive"))
    )
    (net (code "173") (name "unconnected-(U1-Pad128)") (class "Default")
      (node (ref "U1") (pin "128") (pinfunction "128_128") (pintype "passive"))
    )
    (net (code "174") (name "unconnected-(U1-Pad129)") (class "Default")
      (node (ref "U1") (pin "129") (pinfunction "129_129") (pintype "passive"))
    )
    (net (code "175") (name "unconnected-(U1-Pad130)") (class "Default")
      (node (ref "U1") (pin "130") (pinfunction "130_130") (pintype "passive"))
    )
    (net (code "176") (name "unconnected-(U1-Pad131)") (class "Default")
      (node (ref "U1") (pin "131") (pinfunction "131_131") (pintype "passive"))
    )
    (net (code "177") (name "unconnected-(U1-Pad132)") (class "Default")
      (node (ref "U1") (pin "132") (pinfunction "132_132") (pintype "passive"))
    )
    (net (code "178") (name "unconnected-(U1-Pad133)") (class "Default")
      (node (ref "U1") (pin "133") (pinfunction "133_133") (pintype "passive"))
    )
    (net (code "179") (name "unconnected-(U1-Pad134)") (class "Default")
      (node (ref "U1") (pin "134") (pinfunction "134_134") (pintype "power_in"))
    )
    (net (code "180") (name "unconnected-(U1-Pad136)") (class "Default")
      (node (ref "U1") (pin "136") (pinfunction "136_136") (pintype "passive"))
    )
    (net (code "181") (name "unconnected-(U1-Pad137)") (class "Default")
      (node (ref "U1") (pin "137") (pinfunction "137_137") (pintype "passive"))
    )
    (net (code "182") (name "unconnected-(U1-Pad138)") (class "Default")
      (node (ref "U1") (pin "138") (pinfunction "138_138") (pintype "passive"))
    )
    (net (code "183") (name "unconnected-(U1-Pad139)") (class "Default")
      (node (ref "U1") (pin "139") (pinfunction "139_139") (pintype "passive"))
    )
    (net (code "184") (name "unconnected-(U1-Pad140)") (class "Default")
      (node (ref "U1") (pin "140") (pinfunction "140_140") (pintype "passive"))
    )
    (net (code "185") (name "unconnected-(U1-Pad141)") (class "Default")
      (node (ref "U1") (pin "141") (pinfunction "141_141") (pintype "passive"))
    )
    (net (code "186") (name "unconnected-(U1-Pad142)") (class "Default")
      (node (ref "U1") (pin "142") (pinfunction "142_142") (pintype "passive"))
    )
    (net (code "187") (name "unconnected-(U1-Pad143)") (class "Default")
      (node (ref "U1") (pin "143") (pinfunction "143_143") (pintype "passive"))
    )
    (net (code "188") (name "unconnected-(U1-Pad144)") (class "Default")
      (node (ref "U1") (pin "144") (pinfunction "144_144") (pintype "passive"))
    )
    (net (code "189") (name "unconnected-(U2-PTA0{slash}IRQ_0-Pad14)") (class "Default")
      (node (ref "U2") (pin "14") (pinfunction "PTA0/IRQ_0_14") (pintype "bidirectional+no_connect"))
    )
    (net (code "190") (name "unconnected-(U2-PTA1{slash}IRQ_1{slash}LPTMR0_ALT1-Pad15)") (class "Default")
      (node (ref "U2") (pin "15") (pinfunction "PTA1/IRQ_1/LPTMR0_ALT1_15") (pintype "bidirectional+no_connect"))
    )
    (net (code "191") (name "unconnected-(U2-PTA2-Pad16)") (class "Default")
      (node (ref "U2") (pin "16") (pinfunction "PTA2_16") (pintype "bidirectional+no_connect"))
    )
    (net (code "192") (name "unconnected-(U2-PTA3-Pad3)") (class "Default")
      (node (ref "U2") (pin "3") (pinfunction "PTA3_3") (pintype "bidirectional+no_connect"))
    )
    (net (code "193") (name "unconnected-(U2-PTA5-Pad5)") (class "Default")
      (node (ref "U2") (pin "5") (pinfunction "PTA5_5") (pintype "bidirectional+no_connect"))
    )
    (net (code "194") (name "unconnected-(U2-PTB3{slash}IRQ_10-Pad11)") (class "Default")
      (node (ref "U2") (pin "11") (pinfunction "PTB3/IRQ_10_11") (pintype "bidirectional+no_connect"))
    )
    (net (code "195") (name "unconnected-(U2-PTB4{slash}IRQ_11-Pad12)") (class "Default")
      (node (ref "U2") (pin "12") (pinfunction "PTB4/IRQ_11_12") (pintype "bidirectional+no_connect"))
    )
    (net (code "196") (name "unconnected-(U3-NC-Pad3)") (class "Default")
      (node (ref "U3") (pin "3") (pinfunction "NC_3") (pintype "passive+no_connect"))
    )
    (net (code "197") (name "unconnected-(oscillator1-Pad2)") (class "Default")
      (node (ref "oscillator1") (pin "2") (pinfunction "2_2") (pintype "passive+no_connect"))
    )
    (net (code "198") (name "unconnected-(oscillator1-Pad4)") (class "Default")
      (node (ref "oscillator1") (pin "4") (pinfunction "4_4") (pintype "passive+no_connect"))
    )
  )
)
